# NeuroBB.net
KiCad netlist of a schematic drawn in Altium Designer
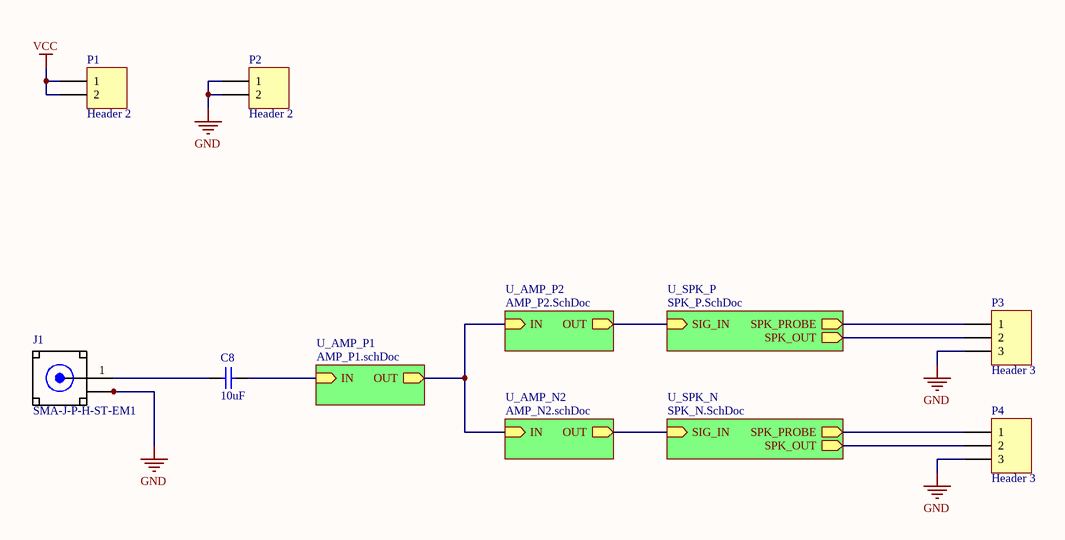
[diagram p0: NeuroBB.SchDoc]

(export (version "E")
  (design (tool "Eeschema 10.0.6"))
  (components
    (comp (ref "C8")
      (value "10uF")
      (footprint "SMD-0603")
      (description "Ceramic Capacitor 0603")
      (libsource (lib "LCR") (part "CAP0603"))
    )
    (comp (ref "J1")
      (value "SMA-J-P-H-ST-EM1")
      (footprint "SMA-J-P-H-ST-EM1")
      (description "Connector SMA F 50Ohm Solder ST Edge Mount Gold Over Nickel Tray")
      (fields (field (name "MF") "Samtec"))
      (libsource (lib "Connectors") (part "SMA-J-P-H-ST-EM1"))
    )
    (comp (ref "P1")
      (value "Header 2")
      (footprint "HDR1X2")
      (description "Header, 2-Pin")
      (fields (field (name "PUBLISHER") "Altium Limited"))
      (libsource (lib "Miscellaneous Connectors") (part "Header 2"))
    )
    (comp (ref "P2")
      (value "Header 2")
      (footprint "HDR1X2")
      (description "Header, 2-Pin")
      (fields (field (name "PUBLISHER") "Altium Limited"))
      (libsource (lib "Miscellaneous Connectors") (part "Header 2"))
    )
    (comp (ref "P3")
      (value "Header 3")
      (footprint "HDR1X3")
      (description "Header, 3-Pin")
      (fields (field (name "PUBLISHER") "Altium Limited"))
      (libsource (lib "Miscellaneous Connectors") (part "Header 3"))
    )
    (comp (ref "P4")
      (value "Header 3")
      (footprint "HDR1X3")
      (description "Header, 3-Pin")
      (fields (field (name "PUBLISHER") "Altium Limited"))
      (libsource (lib "Miscellaneous Connectors") (part "Header 3"))
    )
  )
  (nets
    (net (code "1") (name "/IN") (class "Default")
      (node (ref "C8") (pin "2") (pinfunction "2_2") (pintype "passive"))
    )
    (net (code "5") (name "/SPK_OUT") (class "Default")
      (node (ref "P4") (pin "2") (pinfunction "2_2") (pintype "passive"))
    )
    (net (code "6") (name "/SPK_OUT_1") (class "Default")
      (node (ref "P3") (pin "2") (pinfunction "2_2") (pintype "passive"))
    )
    (net (code "7") (name "/SPK_PROBE") (class "Default")
      (node (ref "P4") (pin "1") (pinfunction "1_1") (pintype "passive"))
    )
    (net (code "8") (name "/SPK_PROBE_1") (class "Default")
      (node (ref "P3") (pin "1") (pinfunction "1_1") (pintype "passive"))
    )
    (net (code "9") (name "GND") (class "Default")
      (node (ref "J1") (pin "2_1") (pinfunction "GND_2_1") (pintype "power_in"))
      (node (ref "J1") (pin "2_2") (pinfunction "GND_2_2") (pintype "power_in"))
      (node (ref "J1") (pin "3_1") (pinfunction "GND_3_1") (pintype "power_in"))
      (node (ref "J1") (pin "3_2") (pinfunction "GND_3_2") (pintype "power_in"))
      (node (ref "P2") (pin "1") (pinfunction "1_1") (pintype "passive"))
      (node (ref "P2") (pin "2") (pinfunction "2_2") (pintype "passive"))
      (node (ref "P3") (pin "3") (pinfunction "3_3") (pintype "passive"))
      (node (ref "P4") (pin "3") (pinfunction "3_3") (pintype "passive"))
    )
    (net (code "10") (name "Net-(J1-SIGNAL)") (class "Default")
      (node (ref "C8") (pin "1") (pinfunction "1_1") (pintype "passive"))
      (node (ref "J1") (pin "1") (pinfunction "SIGNAL_1") (pintype "passive"))
    )
    (net (code "11") (name "VCC") (class "Default")
      (node (ref "P1") (pin "1") (pinfunction "1_1") (pintype "passive"))
      (node (ref "P1") (pin "2") (pinfunction "2_2") (pintype "passive"))
    )
  )
)
